# bmx160.net
KiCad netlist of a schematic drawn in EAGLE
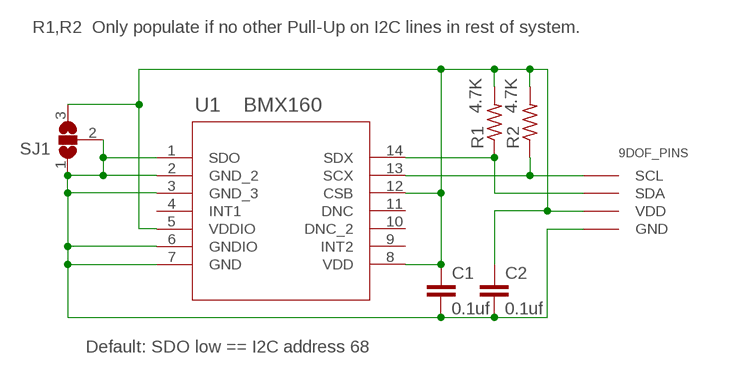
[diagram p0: schematic, sheet 1]

(export (version "E")
  (design (tool "Eeschema 10.0.6"))
  (components
    (comp (ref "C1")
      (value "0.1uf")
      (footprint "eagle-import:C0603K")
      (libsource (lib "eagle-import") (part "C-EUC0603K"))
    )
    (comp (ref "C2")
      (value "0.1uf")
      (footprint "eagle-import:C0603K")
      (libsource (lib "eagle-import") (part "C-EUC0603K"))
    )
    (comp (ref "MOD1")
      (value "9DOF_PINS")
      (footprint "eagle-import:9DOF_PINS")
      (libsource (lib "eagle-import") (part "9DOF_PINS"))
    )
    (comp (ref "R1")
      (value "4.7K")
      (footprint "eagle-import:M0805")
      (libsource (lib "eagle-import") (part "R-US_M0805"))
    )
    (comp (ref "R2")
      (value "4.7K")
      (footprint "eagle-import:M0805")
      (libsource (lib "eagle-import") (part "R-US_M0805"))
    )
    (comp (ref "SJ1")
      (value "SJ2W")
      (footprint "eagle-import:SJ_2")
      (libsource (lib "eagle-import") (part "SJ2W"))
    )
    (comp (ref "U1")
      (value "BMX160")
      (footprint "eagle-import:BMX160_BOS-M")
      (libsource (lib "eagle-import") (part "BMX160BMX160_BOS-M"))
    )
  )
  (nets
    (net (code "1") (name "Net-(U1-CSB)") (class "Default")
      (node (ref "C1") (pin "1") (pinfunction "1_1") (pintype "passive"))
      (node (ref "C2") (pin "1") (pinfunction "1_1") (pintype "passive"))
      (node (ref "MOD1") (pin "VDD") (pinfunction "VDD_VDD") (pintype "power_in"))
      (node (ref "R1") (pin "2") (pinfunction "2_2") (pintype "passive"))
      (node (ref "R2") (pin "2") (pinfunction "2_2") (pintype "passive"))
      (node (ref "SJ1") (pin "3") (pinfunction "3_3") (pintype "passive"))
      (node (ref "U1") (pin "12") (pinfunction "CSB_12") (pintype "passive"))
      (node (ref "U1") (pin "5") (pinfunction "VDDIO_5") (pintype "passive"))
      (node (ref "U1") (pin "8") (pinfunction "VDD_8") (pintype "passive"))
    )
    (net (code "2") (name "Net-(U1-GND)") (class "Default")
      (node (ref "C1") (pin "2") (pinfunction "2_2") (pintype "passive"))
      (node (ref "C2") (pin "2") (pinfunction "2_2") (pintype "passive"))
      (node (ref "MOD1") (pin "GND") (pinfunction "GND_GND") (pintype "power_in"))
      (node (ref "SJ1") (pin "1") (pinfunction "1_1") (pintype "passive"))
      (node (ref "SJ1") (pin "2") (pinfunction "2_2") (pintype "passive"))
      (node (ref "U1") (pin "1") (pinfunction "SDO_1") (pintype "passive"))
      (node (ref "U1") (pin "2") (pinfunction "GND_2_2") (pintype "passive"))
      (node (ref "U1") (pin "3") (pinfunction "GND_3_3") (pintype "passive"))
      (node (ref "U1") (pin "6") (pinfunction "GNDIO_6") (pintype "passive"))
      (node (ref "U1") (pin "7") (pinfunction "GND_7") (pintype "passive"))
    )
    (net (code "3") (name "Net-(U1-SCX)") (class "Default")
      (node (ref "MOD1") (pin "SCL") (pinfunction "SCL_SCL") (pintype "bidirectional"))
      (node (ref "R2") (pin "1") (pinfunction "1_1") (pintype "passive"))
      (node (ref "U1") (pin "13") (pinfunction "SCX_13") (pintype "passive"))
    )
    (net (code "4") (name "Net-(U1-SDX)") (class "Default")
      (node (ref "MOD1") (pin "SDA") (pinfunction "SDA_SDA") (pintype "bidirectional"))
      (node (ref "R1") (pin "1") (pinfunction "1_1") (pintype "passive"))
      (node (ref "U1") (pin "14") (pinfunction "SDX_14") (pintype "passive"))
    )
    (net (code "5") (name "unconnected-(U1-DNC-Pad11)") (class "Default")
      (node (ref "U1") (pin "11") (pinfunction "DNC_11") (pintype "passive"))
    )
    (net (code "6") (name "unconnected-(U1-DNC_2-Pad10)") (class "Default")
      (node (ref "U1") (pin "10") (pinfunction "DNC_2_10") (pintype "passive"))
    )
    (net (code "7") (name "unconnected-(U1-INT1-Pad4)") (class "Default")
      (node (ref "U1") (pin "4") (pinfunction "INT1_4") (pintype "passive"))
    )
    (net (code "8") (name "unconnected-(U1-INT2-Pad9)") (class "Default")
      (node (ref "U1") (pin "9") (pinfunction "INT2_9") (pintype "passive"))
    )
  )
)
